# MR_UartConnector.net
KiCad netlist of a schematic drawn in Altium Designer
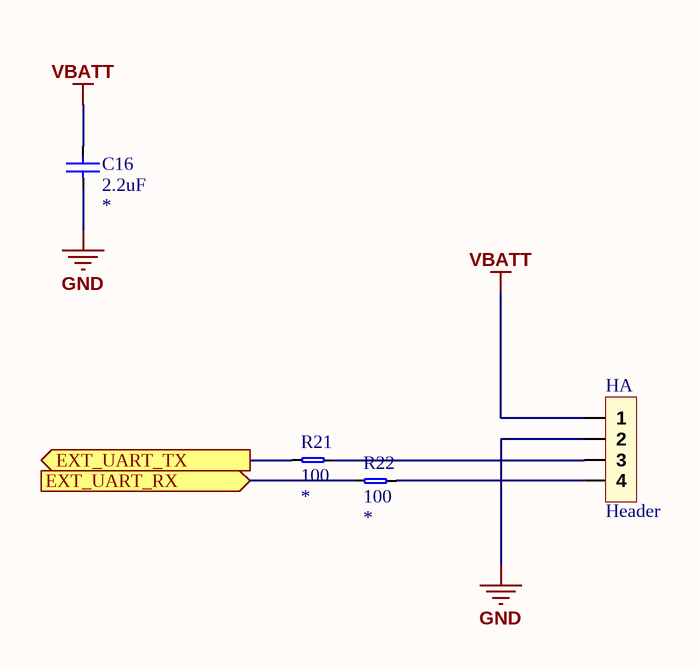
[diagram p0: MR_UartConnector.SchDoc]

(export (version "E")
  (design (tool "Eeschema 10.0.6"))
  (components
    (comp (ref "C16")
      (value "2.2uF")
      (footprint "0603_CAP_LD")
      (description "Ceramic Capacitor")
      (fields (field (name "PACKAGE") "*") (field (name "Comment") "CerCap"))
      (libsource (lib "MiniRobot") (part "CerCap"))
    )
    (comp (ref "HA")
      (value "Header")
      (footprint "HE14 1x4 Straight")
      (description "Header 4x1 PIns")
      (libsource (lib "MiniRobot") (part "Header_4x1"))
    )
    (comp (ref "R21")
      (value "100")
      (footprint "0603_RES_LD")
      (description "Resistor")
      (fields (field (name "PACKAGE") "*"))
      (libsource (lib "MiniRobot") (part "Resistor"))
    )
    (comp (ref "R22")
      (value "100")
      (footprint "0603_RES_LD")
      (description "Resistor")
      (fields (field (name "PACKAGE") "*"))
      (libsource (lib "MiniRobot") (part "Resistor"))
    )
  )
  (nets
    (net (code "1") (name "/EXT_UART_RX") (class "Default")
      (node (ref "R22") (pin "1") (pinfunction "1_1") (pintype "passive"))
    )
    (net (code "2") (name "/EXT_UART_TX") (class "Default")
      (node (ref "R21") (pin "1") (pinfunction "1_1") (pintype "passive"))
    )
    (net (code "3") (name "GND") (class "Default")
      (node (ref "C16") (pin "1") (pinfunction "1_1") (pintype "passive"))
      (node (ref "HA") (pin "2") (pinfunction "2_2") (pintype "passive"))
    )
    (net (code "4") (name "Net-(HA-Pad3)") (class "Default")
      (node (ref "HA") (pin "3") (pinfunction "3_3") (pintype "passive"))
      (node (ref "R21") (pin "2") (pinfunction "2_2") (pintype "passive"))
    )
    (net (code "5") (name "Net-(HA-Pad4)") (class "Default")
      (node (ref "HA") (pin "4") (pinfunction "4_4") (pintype "passive"))
      (node (ref "R22") (pin "2") (pinfunction "2_2") (pintype "passive"))
    )
    (net (code "6") (name "VBATT") (class "Default")
      (node (ref "C16") (pin "2") (pinfunction "2_2") (pintype "passive"))
      (node (ref "HA") (pin "1") (pinfunction "1_1") (pintype "passive"))
    )
  )
)
